# Glove_PCB.net
KiCad netlist of a schematic drawn in Altium Designer
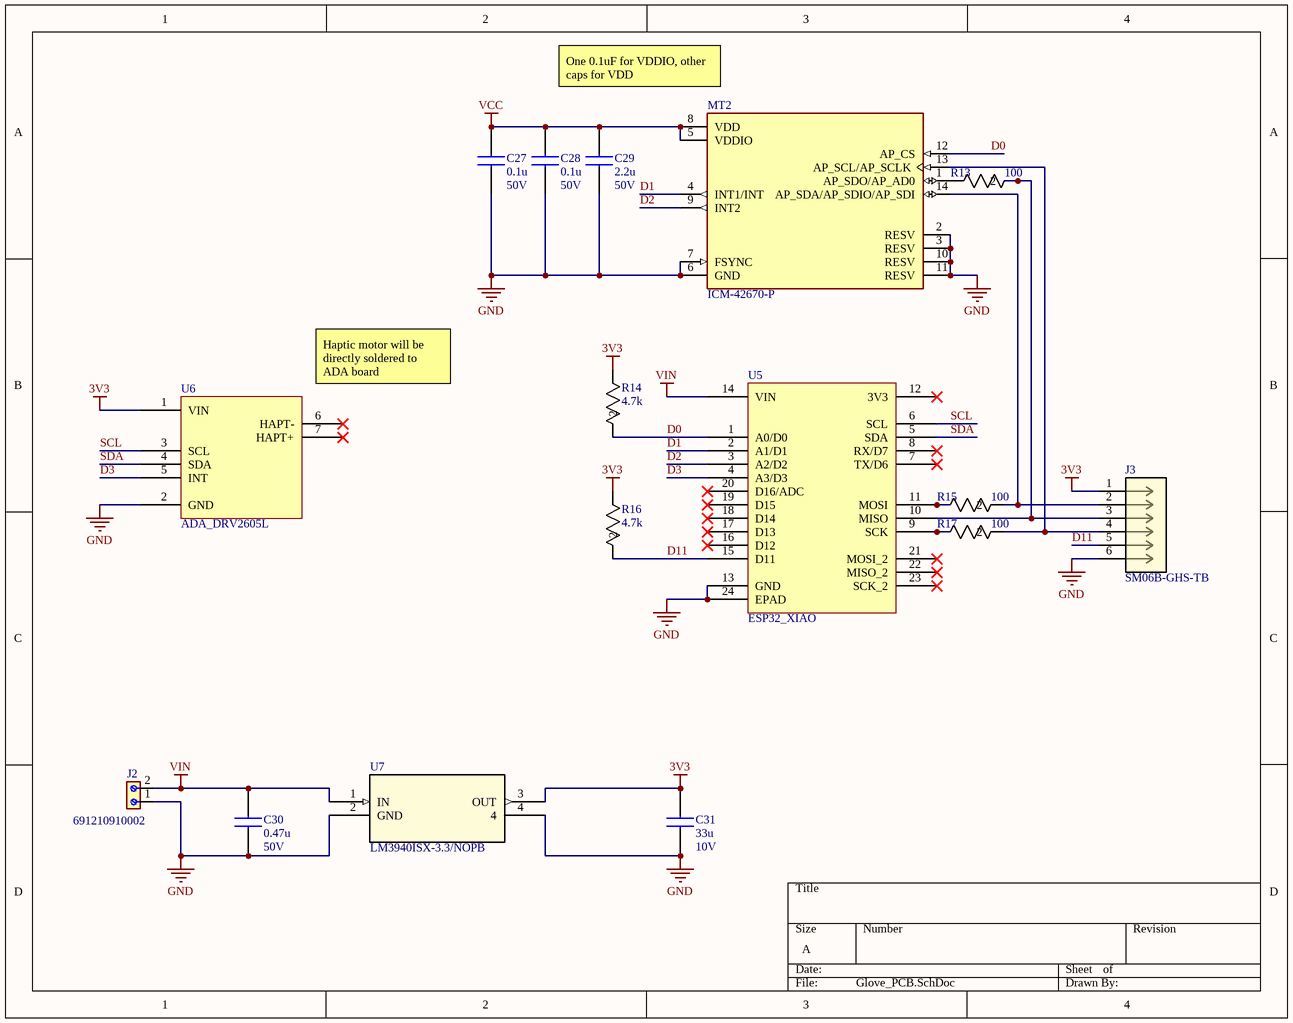
[diagram p0: Glove_PCB.SchDoc]

(export (version "E")
  (design (tool "Eeschema 10.0.6"))
  (components
    (comp (ref "C27")
      (value "0.1u")
      (footprint "CAPC2012X145N")
      (description "Multilayer Ceramic Chip Capacitors, Capacitance=0.1u")
      (fields
        (field (name "MANUFACTURER_PART_NUMBER") "KAM21BR71H104JM")
        (field (name "RATED VOLTAGE") "50V")
      )
      (libsource (lib "Caps") (part "KAM21BR71H104JM"))
    )
    (comp (ref "C28")
      (value "0.1u")
      (footprint "CAPC2012X145N")
      (description "Multilayer Ceramic Chip Capacitors, Capacitance=0.1u")
      (fields
        (field (name "MANUFACTURER_PART_NUMBER") "KAM21BR71H104JM")
        (field (name "RATED VOLTAGE") "50V")
      )
      (libsource (lib "Caps") (part "KAM21BR71H104JM"))
    )
    (comp (ref "C29")
      (value "2.2u")
      (footprint "CAPC2012X145N")
      (description "Multilayer Ceramic Chip Capacitors, Capacitance=2.2u")
      (fields
        (field (name "MANUFACTURER_PART_NUMBER") "C2012X7R1H225K125AE")
        (field (name "RATED VOLTAGE") "50V")
      )
      (libsource (lib "Caps") (part "C2012X7R1H225K125AE"))
    )
    (comp (ref "C30")
      (value "0.47u")
      (footprint "CAPC2012X145N")
      (description "Multilayer Ceramic Chip Capacitors, Capacitance=0.47u")
      (fields
        (field (name "MANUFACTURER_PART_NUMBER") "GCM21BR71H474KA55K")
        (field (name "RATED VOLTAGE") "50V")
      )
      (libsource (lib "Caps") (part "GCM21BR71H474KA55K"))
    )
    (comp (ref "C31")
      (value "33u")
      (footprint "CAPC2012X145N")
      (description "Multilayer Ceramic Chip Capacitors, Capacitance=33u")
      (fields
        (field (name "MANUFACTURER_PART_NUMBER") "C2012X5R1A336M125AC")
        (field (name "RATED VOLTAGE") "10V")
      )
      (libsource (lib "Caps") (part "C2012X5R1A336M125AC"))
    )
    (comp (ref "J2")
      (value "691210910002")
      (footprint "691210910002")
      (fields (field (name "MF") "{'manufacturer': u'~{W}xfcrth Elektronik'}"))
      (libsource (lib "691210910002") (part "691210910002"))
    )
    (comp (ref "J3")
      (value "SM06B-GHS-TB")
      (footprint "CONN_SM06B-GHS-TB_JST")
      (description "No Description Available")
      (fields (field (name "COPYRIGHT") "Copyright (C) 2025 Ultra Librarian. All rights reserved."))
      (libsource (lib "SM06B-GHS-TB") (part "SM06B-GHS-TB"))
    )
    (comp (ref "MT2")
      (value "ICM-42670-P")
      (footprint "XDCR_ICM-42670-P")
      (libsource (lib "ICM-42670-P") (part "ICM-42670-P"))
    )
    (comp (ref "R13")
      (value "100")
      (footprint "RC0805N_YAG")
      (description "RES 0805 100 5% 1/8W")
      (fields (field (name "MANUFACTURER_PART_NUMBER") "RC0805JR-07100RL") (field (name "TOLERANCE") "5%"))
      (libsource (lib "Resistors") (part "RC0805JR-07100RL"))
    )
    (comp (ref "R14")
      (value "4.7k")
      (footprint "RC0805N_YAG")
      (description "RES 0805 4.7k 5% 1/8W")
      (fields (field (name "MANUFACTURER_PART_NUMBER") "RC0805JR-074K7L") (field (name "TOLERANCE") "5%"))
      (libsource (lib "Resistors") (part "RC0805JR-074K7L"))
    )
    (comp (ref "R15")
      (value "100")
      (footprint "RC0805N_YAG")
      (description "RES 0805 100 5% 1/8W")
      (fields (field (name "MANUFACTURER_PART_NUMBER") "RC0805JR-07100RL") (field (name "TOLERANCE") "5%"))
      (libsource (lib "Resistors") (part "RC0805JR-07100RL"))
    )
    (comp (ref "R16")
      (value "4.7k")
      (footprint "RC0805N_YAG")
      (description "RES 0805 4.7k 5% 1/8W")
      (fields (field (name "MANUFACTURER_PART_NUMBER") "RC0805JR-074K7L") (field (name "TOLERANCE") "5%"))
      (libsource (lib "Resistors") (part "RC0805JR-074K7L"))
    )
    (comp (ref "R17")
      (value "100")
      (footprint "RC0805N_YAG")
      (description "RES 0805 100 5% 1/8W")
      (fields (field (name "MANUFACTURER_PART_NUMBER") "RC0805JR-07100RL") (field (name "TOLERANCE") "5%"))
      (libsource (lib "Resistors") (part "RC0805JR-07100RL"))
    )
    (comp (ref "U5")
      (value "ESP32_XIAO")
      (footprint "MOUDLE23P-SMD-2.54-21X17.8MM.kicad_mod.kicad_sym")
      (libsource (lib "ESP32") (part "ESP32_XIAO"))
    )
    (comp (ref "U6")
      (value "ADA_DRV2605L")
      (footprint "ADA_DRV2605L")
      (libsource (lib "ADA_DRV2605L") (part "ADA_DRV2605L"))
    )
    (comp (ref "U7")
      (value "LM3940ISX-3.3/NOPB")
      (footprint "TS3B")
      (description "1-A, low-dropout voltage regulator for 5-V to 3.3-V conversion 3-DDPAK/TO-263 -40 to 125")
      (fields (field (name "COPYRIGHT") "Copyright (C) 2025 Ultra Librarian. All rights reserved."))
      (libsource (lib "LM3940ISX-3P3NOPB") (part "LM3940ISX-3.3NOPB"))
    )
  )
  (nets
    (net (code "1") (name "/D0") (class "Default")
      (node (ref "MT2") (pin "12") (pinfunction "AP_CS_12") (pintype "input"))
      (node (ref "R14") (pin "2") (pinfunction "2_2") (pintype "passive"))
      (node (ref "U5") (pin "1") (pinfunction "A0/D0_1") (pintype "passive"))
    )
    (net (code "2") (name "/D1") (class "Default")
      (node (ref "MT2") (pin "4") (pinfunction "INT1/INT_4") (pintype "output"))
      (node (ref "U5") (pin "2") (pinfunction "A1/D1_2") (pintype "passive"))
    )
    (net (code "3") (name "/D2") (class "Default")
      (node (ref "MT2") (pin "9") (pinfunction "INT2_9") (pintype "output"))
      (node (ref "U5") (pin "3") (pinfunction "A2/D2_3") (pintype "passive"))
    )
    (net (code "4") (name "/D3") (class "Default")
      (node (ref "U5") (pin "4") (pinfunction "A3/D3_4") (pintype "passive"))
      (node (ref "U6") (pin "5") (pinfunction "INT_5") (pintype "passive"))
    )
    (net (code "5") (name "/D11") (class "Default")
      (node (ref "J3") (pin "5") (pinfunction "5_5") (pintype "passive"))
      (node (ref "R16") (pin "2") (pinfunction "2_2") (pintype "passive"))
      (node (ref "U5") (pin "15") (pinfunction "D11_15") (pintype "passive"))
    )
    (net (code "6") (name "/SCL") (class "Default")
      (node (ref "U5") (pin "6") (pinfunction "SCL_6") (pintype "passive"))
      (node (ref "U6") (pin "3") (pinfunction "SCL_3") (pintype "passive"))
    )
    (net (code "7") (name "/SDA") (class "Default")
      (node (ref "U5") (pin "5") (pinfunction "SDA_5") (pintype "passive"))
      (node (ref "U6") (pin "4") (pinfunction "SDA_4") (pintype "passive"))
    )
    (net (code "8") (name "3V3") (class "Default")
      (node (ref "C31") (pin "2") (pinfunction "2_2") (pintype "passive"))
      (node (ref "J3") (pin "1") (pinfunction "1_1") (pintype "passive"))
      (node (ref "R14") (pin "1") (pinfunction "1_1") (pintype "passive"))
      (node (ref "R16") (pin "1") (pinfunction "1_1") (pintype "passive"))
      (node (ref "U6") (pin "1") (pinfunction "VIN_1") (pintype "passive"))
      (node (ref "U7") (pin "3") (pinfunction "OUT_3") (pintype "output"))
    )
    (net (code "9") (name "GND") (class "Default")
      (node (ref "C27") (pin "1") (pinfunction "1_1") (pintype "passive"))
      (node (ref "C28") (pin "1") (pinfunction "1_1") (pintype "passive"))
      (node (ref "C29") (pin "1") (pinfunction "1_1") (pintype "passive"))
      (node (ref "C30") (pin "1") (pinfunction "1_1") (pintype "passive"))
      (node (ref "C31") (pin "1") (pinfunction "1_1") (pintype "passive"))
      (node (ref "J2") (pin "1") (pinfunction "1_1") (pintype "passive"))
      (node (ref "J3") (pin "6") (pinfunction "6_6") (pintype "passive"))
      (node (ref "MT2") (pin "10") (pinfunction "RESV_10") (pintype "passive"))
      (node (ref "MT2") (pin "11") (pinfunction "RESV_11") (pintype "passive"))
      (node (ref "MT2") (pin "2") (pinfunction "RESV_2") (pintype "passive"))
      (node (ref "MT2") (pin "3") (pinfunction "RESV_3") (pintype "passive"))
      (node (ref "MT2") (pin "6") (pinfunction "GND_6") (pintype "power_in"))
      (node (ref "MT2") (pin "7") (pinfunction "FSYNC_7") (pintype "input"))
      (node (ref "U5") (pin "13") (pinfunction "GND_13") (pintype "passive"))
      (node (ref "U5") (pin "24") (pinfunction "EPAD_24") (pintype "passive"))
      (node (ref "U6") (pin "2") (pinfunction "GND_2") (pintype "passive"))
      (node (ref "U7") (pin "2") (pinfunction "GND_2") (pintype "passive"))
      (node (ref "U7") (pin "4") (pinfunction "4_4") (pintype "passive"))
    )
    (net (code "10") (name "Net-(MT2-AP_SCL{slash}AP_SCLK)") (class "Default")
      (node (ref "J3") (pin "4") (pinfunction "4_4") (pintype "passive"))
      (node (ref "MT2") (pin "13") (pinfunction "AP_SCL/AP_SCLK_13") (pintype "input"))
      (node (ref "R17") (pin "2") (pinfunction "2_2") (pintype "passive"))
    )
    (net (code "11") (name "Net-(MT2-AP_SDA{slash}AP_SDIO{slash}AP_SDI)") (class "Default")
      (node (ref "J3") (pin "2") (pinfunction "2_2") (pintype "passive"))
      (node (ref "MT2") (pin "14") (pinfunction "AP_SDA/AP_SDIO/AP_SDI_14") (pintype "bidirectional"))
      (node (ref "R15") (pin "2") (pinfunction "2_2") (pintype "passive"))
    )
    (net (code "12") (name "Net-(MT2-AP_SDO{slash}AP_AD0)") (class "Default")
      (node (ref "MT2") (pin "1") (pinfunction "AP_SDO/AP_AD0_1") (pintype "bidirectional"))
      (node (ref "R13") (pin "1") (pinfunction "1_1") (pintype "passive"))
    )
    (net (code "13") (name "Net-(U5-MISO)") (class "Default")
      (node (ref "J3") (pin "3") (pinfunction "3_3") (pintype "passive"))
      (node (ref "R13") (pin "2") (pinfunction "2_2") (pintype "passive"))
      (node (ref "U5") (pin "10") (pinfunction "MISO_10") (pintype "passive"))
    )
    (net (code "14") (name "Net-(U5-MOSI)") (class "Default")
      (node (ref "R15") (pin "1") (pinfunction "1_1") (pintype "passive"))
      (node (ref "U5") (pin "11") (pinfunction "MOSI_11") (pintype "passive"))
    )
    (net (code "15") (name "Net-(U5-SCK)") (class "Default")
      (node (ref "R17") (pin "1") (pinfunction "1_1") (pintype "passive"))
      (node (ref "U5") (pin "9") (pinfunction "SCK_9") (pintype "passive"))
    )
    (net (code "16") (name "VCC") (class "Default")
      (node (ref "C27") (pin "2") (pinfunction "2_2") (pintype "passive"))
      (node (ref "C28") (pin "2") (pinfunction "2_2") (pintype "passive"))
      (node (ref "C29") (pin "2") (pinfunction "2_2") (pintype "passive"))
      (node (ref "MT2") (pin "5") (pinfunction "VDDIO_5") (pintype "power_in"))
      (node (ref "MT2") (pin "8") (pinfunction "VDD_8") (pintype "power_in"))
    )
    (net (code "17") (name "VIN") (class "Default")
      (node (ref "C30") (pin "2") (pinfunction "2_2") (pintype "passive"))
      (node (ref "J2") (pin "2") (pinfunction "2_2") (pintype "passive"))
      (node (ref "U5") (pin "14") (pinfunction "VIN_14") (pintype "passive"))
      (node (ref "U7") (pin "1") (pinfunction "IN_1") (pintype "input"))
    )
    (net (code "18") (name "unconnected-(U5-3V3-Pad12)") (class "Default")
      (node (ref "U5") (pin "12") (pinfunction "3V3_12") (pintype "passive+no_connect"))
    )
    (net (code "19") (name "unconnected-(U5-D12-Pad16)") (class "Default")
      (node (ref "U5") (pin "16") (pinfunction "D12_16") (pintype "passive+no_connect"))
    )
    (net (code "20") (name "unconnected-(U5-D13-Pad17)") (class "Default")
      (node (ref "U5") (pin "17") (pinfunction "D13_17") (pintype "passive+no_connect"))
    )
    (net (code "21") (name "unconnected-(U5-D14-Pad18)") (class "Default")
      (node (ref "U5") (pin "18") (pinfunction "D14_18") (pintype "passive+no_connect"))
    )
    (net (code "22") (name "unconnected-(U5-D15-Pad19)") (class "Default")
      (node (ref "U5") (pin "19") (pinfunction "D15_19") (pintype "passive+no_connect"))
    )
    (net (code "23") (name "unconnected-(U5-D16{slash}ADC-Pad20)") (class "Default")
      (node (ref "U5") (pin "20") (pinfunction "D16/ADC_20") (pintype "passive+no_connect"))
    )
    (net (code "24") (name "unconnected-(U5-MISO_2-Pad22)") (class "Default")
      (node (ref "U5") (pin "22") (pinfunction "MISO_2_22") (pintype "passive+no_connect"))
    )
    (net (code "25") (name "unconnected-(U5-MOSI_2-Pad21)") (class "Default")
      (node (ref "U5") (pin "21") (pinfunction "MOSI_2_21") (pintype "passive+no_connect"))
    )
    (net (code "26") (name "unconnected-(U5-RX{slash}D7-Pad8)") (class "Default")
      (node (ref "U5") (pin "8") (pinfunction "RX/D7_8") (pintype "passive+no_connect"))
    )
    (net (code "27") (name "unconnected-(U5-SCK_2-Pad23)") (class "Default")
      (node (ref "U5") (pin "23") (pinfunction "SCK_2_23") (pintype "passive+no_connect"))
    )
    (net (code "28") (name "unconnected-(U5-TX{slash}D6-Pad7)") (class "Default")
      (node (ref "U5") (pin "7") (pinfunction "TX/D6_7") (pintype "passive+no_connect"))
    )
    (net (code "29") (name "unconnected-(U6-HAPT+-Pad7)") (class "Default")
      (node (ref "U6") (pin "7") (pinfunction "HAPT+_7") (pintype "passive+no_connect"))
    )
    (net (code "30") (name "unconnected-(U6-HAPT--Pad6)") (class "Default")
      (node (ref "U6") (pin "6") (pinfunction "HAPT-_6") (pintype "passive+no_connect"))
    )
  )
)
